# GPS_Module.net
KiCad netlist of a schematic drawn in EAGLE
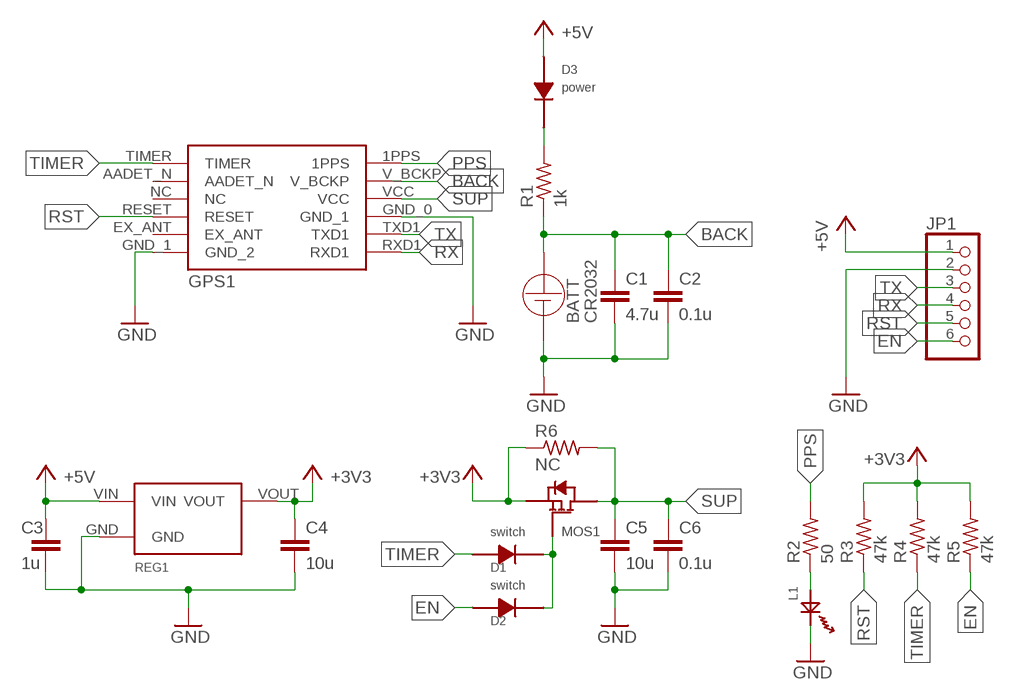
[diagram p0: schematic, sheet 1]

(export (version "E")
  (design (tool "Eeschema 10.0.6"))
  (components
    (comp (ref "BATT")
      (value "CR2032")
      (footprint "eagle-import:CR2032")
      (libsource (lib "eagle-import") (part "CR2032"))
    )
    (comp (ref "C1")
      (value "4.7u")
      (footprint "eagle-import:C0603")
      (libsource (lib "eagle-import") (part "C-EUC0603"))
    )
    (comp (ref "C2")
      (value "0.1u")
      (footprint "eagle-import:C0603")
      (libsource (lib "eagle-import") (part "C-EUC0603"))
    )
    (comp (ref "C3")
      (value "1u")
      (footprint "eagle-import:C0603")
      (libsource (lib "eagle-import") (part "C-EUC0603"))
    )
    (comp (ref "C4")
      (value "10u")
      (footprint "eagle-import:C0603")
      (libsource (lib "eagle-import") (part "C-EUC0603"))
    )
    (comp (ref "C5")
      (value "10u")
      (footprint "eagle-import:C0603")
      (libsource (lib "eagle-import") (part "C-EUC0603"))
    )
    (comp (ref "C6")
      (value "0.1u")
      (footprint "eagle-import:C0603")
      (libsource (lib "eagle-import") (part "C-EUC0603"))
    )
    (comp (ref "D1")
      (value "switch")
      (footprint "eagle-import:SOD-123")
      (libsource (lib "eagle-import") (part "1W4148W"))
    )
    (comp (ref "D2")
      (value "switch")
      (footprint "eagle-import:SOD-123")
      (libsource (lib "eagle-import") (part "1W4148W"))
    )
    (comp (ref "D3")
      (value "power")
      (footprint "eagle-import:SOD-123FL")
      (libsource (lib "eagle-import") (part "SS2040FL"))
    )
    (comp (ref "GPS1")
      (value "L80-M39")
      (footprint "eagle-import:L80")
      (libsource (lib "eagle-import") (part "L80-M39"))
    )
    (comp (ref "JP1")
      (value "PINHD-1X6")
      (footprint "eagle-import:1X06")
      (libsource (lib "eagle-import") (part "PINHD-1X6"))
    )
    (comp (ref "L1")
      (value "OSXX1608C1A")
      (footprint "eagle-import:OSXX1608C1A")
      (libsource (lib "eagle-import") (part "OSXX1608C1A"))
    )
    (comp (ref "MOS1")
      (value "AO3401A")
      (footprint "eagle-import:SOT-23")
      (libsource (lib "eagle-import") (part "AO3401A"))
    )
    (comp (ref "R1")
      (value "1k")
      (footprint "eagle-import:R0603")
      (libsource (lib "eagle-import") (part "R-US_R0603"))
    )
    (comp (ref "R2")
      (value "50")
      (footprint "eagle-import:R0805")
      (libsource (lib "eagle-import") (part "R-US_R0805"))
    )
    (comp (ref "R3")
      (value "47k")
      (footprint "eagle-import:R0805")
      (libsource (lib "eagle-import") (part "R-US_R0805"))
    )
    (comp (ref "R4")
      (value "47k")
      (footprint "eagle-import:R0805")
      (libsource (lib "eagle-import") (part "R-US_R0805"))
    )
    (comp (ref "R5")
      (value "47k")
      (footprint "eagle-import:R0805")
      (libsource (lib "eagle-import") (part "R-US_R0805"))
    )
    (comp (ref "R6")
      (value "NC")
      (footprint "eagle-import:R0603")
      (libsource (lib "eagle-import") (part "R-US_R0603"))
    )
    (comp (ref "REG1")
      (value "AP7375")
      (footprint "eagle-import:SOT23")
      (libsource (lib "eagle-import") (part "AP7375"))
    )
  )
  (nets
    (net (code "1") (name "+3V3") (class "Default")
      (node (ref "C4") (pin "1") (pinfunction "1_1") (pintype "passive"))
      (node (ref "MOS1") (pin "S") (pinfunction "S_S") (pintype "bidirectional"))
      (node (ref "R3") (pin "2") (pinfunction "2_2") (pintype "passive"))
      (node (ref "R4") (pin "2") (pinfunction "2_2") (pintype "passive"))
      (node (ref "R5") (pin "2") (pinfunction "2_2") (pintype "passive"))
      (node (ref "R6") (pin "1") (pinfunction "1_1") (pintype "passive"))
      (node (ref "REG1") (pin "VOUT") (pinfunction "VOUT_VOUT") (pintype "bidirectional"))
    )
    (net (code "2") (name "+5V") (class "Default")
      (node (ref "C3") (pin "1") (pinfunction "1_1") (pintype "passive"))
      (node (ref "D3") (pin "C") (pinfunction "C_C") (pintype "bidirectional"))
      (node (ref "JP1") (pin "1") (pinfunction "1_1") (pintype "passive"))
      (node (ref "REG1") (pin "VIN") (pinfunction "VIN_VIN") (pintype "bidirectional"))
    )
    (net (code "3") (name "BACK") (class "Default")
      (node (ref "BATT") (pin "VCC") (pinfunction "VCC_VCC") (pintype "bidirectional"))
      (node (ref "BATT") (pin "VCC2") (pinfunction "VCC_VCC2") (pintype "bidirectional"))
      (node (ref "C1") (pin "1") (pinfunction "1_1") (pintype "passive"))
      (node (ref "C2") (pin "1") (pinfunction "1_1") (pintype "passive"))
      (node (ref "GPS1") (pin "V_BCKP") (pinfunction "V_BCKP_V_BCKP") (pintype "bidirectional"))
      (node (ref "R1") (pin "1") (pinfunction "1_1") (pintype "passive"))
    )
    (net (code "4") (name "EN") (class "Default")
      (node (ref "D2") (pin "C") (pinfunction "C_C") (pintype "bidirectional"))
      (node (ref "JP1") (pin "6") (pinfunction "6_6") (pintype "passive"))
      (node (ref "R5") (pin "1") (pinfunction "1_1") (pintype "passive"))
    )
    (net (code "5") (name "GND") (class "Default")
      (node (ref "BATT") (pin "GND") (pinfunction "GND_GND") (pintype "bidirectional"))
      (node (ref "C1") (pin "2") (pinfunction "2_2") (pintype "passive"))
      (node (ref "C2") (pin "2") (pinfunction "2_2") (pintype "passive"))
      (node (ref "C3") (pin "2") (pinfunction "2_2") (pintype "passive"))
      (node (ref "C4") (pin "2") (pinfunction "2_2") (pintype "passive"))
      (node (ref "C5") (pin "2") (pinfunction "2_2") (pintype "passive"))
      (node (ref "C6") (pin "2") (pinfunction "2_2") (pintype "passive"))
      (node (ref "GPS1") (pin "GND_0") (pinfunction "GND_1_GND_0") (pintype "bidirectional"))
      (node (ref "GPS1") (pin "GND_1") (pinfunction "GND_2_GND_1") (pintype "bidirectional"))
      (node (ref "JP1") (pin "2") (pinfunction "2_2") (pintype "passive"))
      (node (ref "L1") (pin "CT") (pinfunction "CT_CT") (pintype "bidirectional"))
      (node (ref "REG1") (pin "GND") (pinfunction "GND_GND") (pintype "bidirectional"))
    )
    (net (code "6") (name "Net-(D1-PadA)") (class "Default")
      (node (ref "D1") (pin "A") (pinfunction "A_A") (pintype "bidirectional"))
      (node (ref "D2") (pin "A") (pinfunction "A_A") (pintype "bidirectional"))
      (node (ref "MOS1") (pin "G") (pinfunction "G_G") (pintype "bidirectional"))
    )
    (net (code "7") (name "Net-(D3-PadA)") (class "Default")
      (node (ref "D3") (pin "A") (pinfunction "A_A") (pintype "bidirectional"))
      (node (ref "R1") (pin "2") (pinfunction "2_2") (pintype "passive"))
    )
    (net (code "8") (name "Net-(L1-PadAN)") (class "Default")
      (node (ref "L1") (pin "AN") (pinfunction "AN_AN") (pintype "bidirectional"))
      (node (ref "R2") (pin "1") (pinfunction "1_1") (pintype "passive"))
    )
    (net (code "9") (name "PPS") (class "Default")
      (node (ref "GPS1") (pin "1PPS") (pinfunction "1PPS_1PPS") (pintype "bidirectional"))
      (node (ref "R2") (pin "2") (pinfunction "2_2") (pintype "passive"))
    )
    (net (code "10") (name "RST") (class "Default")
      (node (ref "GPS1") (pin "RESET") (pinfunction "RESET_RESET") (pintype "bidirectional"))
      (node (ref "JP1") (pin "5") (pinfunction "5_5") (pintype "passive"))
      (node (ref "R3") (pin "1") (pinfunction "1_1") (pintype "passive"))
    )
    (net (code "11") (name "RX") (class "Default")
      (node (ref "GPS1") (pin "RXD1") (pinfunction "RXD1_RXD1") (pintype "bidirectional"))
      (node (ref "JP1") (pin "4") (pinfunction "4_4") (pintype "passive"))
    )
    (net (code "12") (name "SUP") (class "Default")
      (node (ref "C5") (pin "1") (pinfunction "1_1") (pintype "passive"))
      (node (ref "C6") (pin "1") (pinfunction "1_1") (pintype "passive"))
      (node (ref "GPS1") (pin "VCC") (pinfunction "VCC_VCC") (pintype "bidirectional"))
      (node (ref "MOS1") (pin "D") (pinfunction "D_D") (pintype "bidirectional"))
      (node (ref "R6") (pin "2") (pinfunction "2_2") (pintype "passive"))
    )
    (net (code "13") (name "TIMER") (class "Default")
      (node (ref "D1") (pin "C") (pinfunction "C_C") (pintype "bidirectional"))
      (node (ref "GPS1") (pin "TIMER") (pinfunction "TIMER_TIMER") (pintype "bidirectional"))
      (node (ref "R4") (pin "1") (pinfunction "1_1") (pintype "passive"))
    )
    (net (code "14") (name "TX") (class "Default")
      (node (ref "GPS1") (pin "TXD1") (pinfunction "TXD1_TXD1") (pintype "bidirectional"))
      (node (ref "JP1") (pin "3") (pinfunction "3_3") (pintype "passive"))
    )
    (net (code "15") (name "unconnected-(GPS1-PadAADET_N)") (class "Default")
      (node (ref "GPS1") (pin "AADET_N") (pinfunction "AADET_N_AADET_N") (pintype "bidirectional"))
    )
    (net (code "16") (name "unconnected-(GPS1-PadEX_ANT)") (class "Default")
      (node (ref "GPS1") (pin "EX_ANT") (pinfunction "EX_ANT_EX_ANT") (pintype "bidirectional"))
    )
    (net (code "17") (name "unconnected-(GPS1-PadNC)") (class "Default")
      (node (ref "GPS1") (pin "NC") (pinfunction "NC_NC") (pintype "bidirectional"))
    )
  )
)
